# ESP_Link.net
KiCad netlist of a schematic drawn in Altium Designer
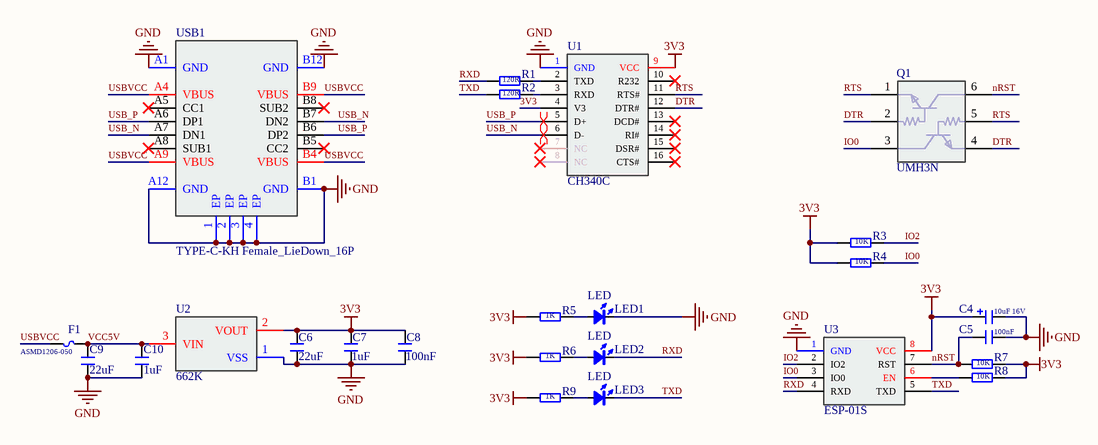
[diagram p0: ESP_Link.SchDoc]

(export (version "E")
  (design (tool "Eeschema 10.0.6"))
  (components
    (comp (ref "C4")
      (value "10uF 16V")
      (footprint "3216TantalumCap")
      (description "3216钽电容")
      (libsource (lib "IntegratedDevices") (part "3216TantalumCap"))
    )
    (comp (ref "C5")
      (value "100nF")
      (footprint "C0603")
      (description "电容-0603")
      (libsource (lib "IntegratedDevices") (part "C0603"))
    )
    (comp (ref "C6")
      (value "22uF")
      (footprint "C0603")
      (description "电容-0603")
      (libsource (lib "IntegratedDevices") (part "C0603"))
    )
    (comp (ref "C7")
      (value "1uF")
      (footprint "C0603")
      (description "电容-0603")
      (libsource (lib "IntegratedDevices") (part "C0603"))
    )
    (comp (ref "C8")
      (value "100nF")
      (footprint "C0603")
      (description "电容-0603")
      (libsource (lib "IntegratedDevices") (part "C0603"))
    )
    (comp (ref "C9")
      (value "22uF")
      (footprint "C0603")
      (description "电容-0603")
      (libsource (lib "IntegratedDevices") (part "C0603"))
    )
    (comp (ref "C10")
      (value "1uF")
      (footprint "C0603")
      (description "电容-0603")
      (libsource (lib "IntegratedDevices") (part "C0603"))
    )
    (comp (ref "F1")
      (value "ASMD1206-050")
      (footprint "ASMD1206-050")
      (description "自恢复保险丝")
      (libsource (lib "IntegratedDevices") (part "ASMD1206-050"))
    )
    (comp (ref "LED1")
      (value "LED")
      (footprint "LED_0603")
      (libsource (lib "IntegratedDevices") (part "LED_0603"))
    )
    (comp (ref "LED2")
      (value "LED")
      (footprint "LED_0603")
      (libsource (lib "IntegratedDevices") (part "LED_0603"))
    )
    (comp (ref "LED3")
      (value "LED")
      (footprint "LED_0603")
      (libsource (lib "IntegratedDevices") (part "LED_0603"))
    )
    (comp (ref "Q1")
      (value "UMH3N")
      (footprint "UMH3N")
      (description "2个NPN预偏压式(双) 100mA 50V")
      (libsource (lib "IntegratedDevices") (part "UMH3N"))
    )
    (comp (ref "R1")
      (value "120R")
      (footprint "R0603")
      (description "电阻-0603")
      (libsource (lib "IntegratedDevices") (part "R0603"))
    )
    (comp (ref "R2")
      (value "120R")
      (footprint "R0603")
      (description "电阻-0603")
      (libsource (lib "IntegratedDevices") (part "R0603"))
    )
    (comp (ref "R3")
      (value "10K")
      (footprint "R0603")
      (description "电阻-0603")
      (libsource (lib "IntegratedDevices") (part "R0603"))
    )
    (comp (ref "R4")
      (value "10K")
      (footprint "R0603")
      (description "电阻-0603")
      (libsource (lib "IntegratedDevices") (part "R0603"))
    )
    (comp (ref "R5")
      (value "1K")
      (footprint "R0603")
      (description "电阻-0603")
      (libsource (lib "IntegratedDevices") (part "R0603"))
    )
    (comp (ref "R6")
      (value "1K")
      (footprint "R0603")
      (description "电阻-0603")
      (libsource (lib "IntegratedDevices") (part "R0603"))
    )
    (comp (ref "R7")
      (value "10K")
      (footprint "R0603")
      (description "电阻-0603")
      (libsource (lib "IntegratedDevices") (part "R0603"))
    )
    (comp (ref "R8")
      (value "10K")
      (footprint "R0603")
      (description "电阻-0603")
      (libsource (lib "IntegratedDevices") (part "R0603"))
    )
    (comp (ref "R9")
      (value "1K")
      (footprint "R0603")
      (description "电阻-0603")
      (libsource (lib "IntegratedDevices") (part "R0603"))
    )
    (comp (ref "U1")
      (value "CH340C")
      (footprint "CH340C")
      (libsource (lib "IntegratedDevices") (part "CH340C"))
    )
    (comp (ref "U2")
      (value "662K")
      (footprint "662K")
      (description "线性稳压器LDO MaxIN: 6V  OUT: 3.3V")
      (libsource (lib "IntegratedDevices") (part "662K"))
    )
    (comp (ref "U3")
      (value "ESP-01S")
      (footprint "ESP-01S-NoSlik")
      (description "ESP01S开发板")
      (libsource (lib "IntegratedDevices") (part "ESP-01S"))
    )
    (comp (ref "USB1")
      (value "TYPE-C-KH Female_LieDown_16P")
      (footprint "TYPE-C-KH Female_LieDown_16P")
      (description "Type-C母座_卧贴_16P")
      (libsource (lib "IntegratedDevices") (part "TYPE-C-KH Female_LieDown_16P"))
    )
  )
  (nets
    (net (code "1") (name "/DTR") (class "Default")
      (node (ref "Q1") (pin "2") (pinfunction "B_2") (pintype "passive"))
      (node (ref "Q1") (pin "4") (pinfunction "E_4") (pintype "passive"))
      (node (ref "U1") (pin "12") (pinfunction "DTR#_12") (pintype "passive"))
    )
    (net (code "2") (name "/IO0") (class "Default")
      (node (ref "Q1") (pin "3") (pinfunction "C_3") (pintype "passive"))
      (node (ref "R4") (pin "2") (pinfunction "2_2") (pintype "passive"))
      (node (ref "U3") (pin "3") (pinfunction "IO0_3") (pintype "passive"))
    )
    (net (code "3") (name "/IO2") (class "Default")
      (node (ref "R3") (pin "2") (pinfunction "2_2") (pintype "passive"))
      (node (ref "U3") (pin "2") (pinfunction "IO2_2") (pintype "passive"))
    )
    (net (code "4") (name "/RTS") (class "Default")
      (node (ref "Q1") (pin "1") (pinfunction "E_1") (pintype "passive"))
      (node (ref "Q1") (pin "5") (pinfunction "B_5") (pintype "passive"))
      (node (ref "U1") (pin "11") (pinfunction "RTS#_11") (pintype "passive"))
    )
    (net (code "5") (name "/RXD") (class "Default")
      (node (ref "LED2") (pin "2") (pinfunction "K_2") (pintype "passive"))
      (node (ref "R1") (pin "2") (pinfunction "2_2") (pintype "passive"))
      (node (ref "U3") (pin "4") (pinfunction "RXD_4") (pintype "passive"))
    )
    (net (code "6") (name "/TXD") (class "Default")
      (node (ref "LED3") (pin "2") (pinfunction "K_2") (pintype "passive"))
      (node (ref "R2") (pin "2") (pinfunction "2_2") (pintype "passive"))
      (node (ref "U3") (pin "5") (pinfunction "TXD_5") (pintype "passive"))
    )
    (net (code "7") (name "/USBVCC") (class "Default")
      (node (ref "F1") (pin "2") (pinfunction "2_2") (pintype "passive"))
      (node (ref "USB1") (pin "A4") (pinfunction "VBUS_A4") (pintype "passive"))
      (node (ref "USB1") (pin "A9") (pinfunction "VBUS_A9") (pintype "passive"))
      (node (ref "USB1") (pin "B4") (pinfunction "VBUS_B4") (pintype "passive"))
      (node (ref "USB1") (pin "B9") (pinfunction "VBUS_B9") (pintype "passive"))
    )
    (net (code "8") (name "/USB_N") (class "Default")
      (node (ref "U1") (pin "6") (pinfunction "D-_6") (pintype "passive"))
      (node (ref "USB1") (pin "A7") (pinfunction "DN1_A7") (pintype "passive"))
      (node (ref "USB1") (pin "B7") (pinfunction "DN2_B7") (pintype "passive"))
    )
    (net (code "9") (name "/USB_P") (class "Default")
      (node (ref "U1") (pin "5") (pinfunction "D+_5") (pintype "passive"))
      (node (ref "USB1") (pin "A6") (pinfunction "DP1_A6") (pintype "passive"))
      (node (ref "USB1") (pin "B6") (pinfunction "DP2_B6") (pintype "passive"))
    )
    (net (code "10") (name "/VCC5V") (class "Default")
      (node (ref "C10") (pin "2") (pinfunction "2_2") (pintype "passive"))
      (node (ref "C9") (pin "2") (pinfunction "2_2") (pintype "passive"))
      (node (ref "F1") (pin "1") (pinfunction "1_1") (pintype "passive"))
      (node (ref "U2") (pin "3") (pinfunction "VIN_3") (pintype "passive"))
    )
    (net (code "11") (name "/nRST") (class "Default")
      (node (ref "C5") (pin "2") (pinfunction "2_2") (pintype "passive"))
      (node (ref "Q1") (pin "6") (pinfunction "C_6") (pintype "passive"))
      (node (ref "R7") (pin "1") (pinfunction "1_1") (pintype "passive"))
      (node (ref "U3") (pin "7") (pinfunction "RST_7") (pintype "passive"))
    )
    (net (code "12") (name "3V3") (class "Default")
      (node (ref "C4") (pin "1") (pinfunction "1_1") (pintype "passive"))
      (node (ref "C6") (pin "2") (pinfunction "2_2") (pintype "passive"))
      (node (ref "C7") (pin "2") (pinfunction "2_2") (pintype "passive"))
      (node (ref "C8") (pin "2") (pinfunction "2_2") (pintype "passive"))
      (node (ref "R3") (pin "1") (pinfunction "1_1") (pintype "passive"))
      (node (ref "R4") (pin "1") (pinfunction "1_1") (pintype "passive"))
      (node (ref "R5") (pin "1") (pinfunction "1_1") (pintype "passive"))
      (node (ref "R6") (pin "1") (pinfunction "1_1") (pintype "passive"))
      (node (ref "R7") (pin "2") (pinfunction "2_2") (pintype "passive"))
      (node (ref "R8") (pin "2") (pinfunction "2_2") (pintype "passive"))
      (node (ref "R9") (pin "1") (pinfunction "1_1") (pintype "passive"))
      (node (ref "U1") (pin "4") (pinfunction "V3_4") (pintype "passive"))
      (node (ref "U1") (pin "9") (pinfunction "VCC_9") (pintype "passive"))
      (node (ref "U2") (pin "2") (pinfunction "VOUT_2") (pintype "passive"))
      (node (ref "U3") (pin "8") (pinfunction "VCC_8") (pintype "passive"))
    )
    (net (code "13") (name "GND") (class "Default")
      (node (ref "C10") (pin "1") (pinfunction "1_1") (pintype "passive"))
      (node (ref "C4") (pin "2") (pinfunction "2_2") (pintype "passive"))
      (node (ref "C5") (pin "1") (pinfunction "1_1") (pintype "passive"))
      (node (ref "C6") (pin "1") (pinfunction "1_1") (pintype "passive"))
      (node (ref "C7") (pin "1") (pinfunction "1_1") (pintype "passive"))
      (node (ref "C8") (pin "1") (pinfunction "1_1") (pintype "passive"))
      (node (ref "C9") (pin "1") (pinfunction "1_1") (pintype "passive"))
      (node (ref "LED1") (pin "2") (pinfunction "K_2") (pintype "passive"))
      (node (ref "U1") (pin "1") (pinfunction "GND_1") (pintype "passive"))
      (node (ref "U2") (pin "1") (pinfunction "VSS_1") (pintype "passive"))
      (node (ref "U3") (pin "1") (pinfunction "GND_1") (pintype "passive"))
      (node (ref "USB1") (pin "1") (pinfunction "EP_1") (pintype "passive"))
      (node (ref "USB1") (pin "2") (pinfunction "EP_2") (pintype "passive"))
      (node (ref "USB1") (pin "3") (pinfunction "EP_3") (pintype "passive"))
      (node (ref "USB1") (pin "4") (pinfunction "EP_4") (pintype "passive"))
      (node (ref "USB1") (pin "A1") (pinfunction "GND_A1") (pintype "passive"))
      (node (ref "USB1") (pin "A12") (pinfunction "GND_A12") (pintype "passive"))
      (node (ref "USB1") (pin "B1") (pinfunction "GND_B1") (pintype "passive"))
      (node (ref "USB1") (pin "B12") (pinfunction "GND_B12") (pintype "passive"))
    )
    (net (code "14") (name "Net-(LED1-A)") (class "Default")
      (node (ref "LED1") (pin "1") (pinfunction "A_1") (pintype "passive"))
      (node (ref "R5") (pin "2") (pinfunction "2_2") (pintype "passive"))
    )
    (net (code "15") (name "Net-(LED2-A)") (class "Default")
      (node (ref "LED2") (pin "1") (pinfunction "A_1") (pintype "passive"))
      (node (ref "R6") (pin "2") (pinfunction "2_2") (pintype "passive"))
    )
    (net (code "16") (name "Net-(LED3-A)") (class "Default")
      (node (ref "LED3") (pin "1") (pinfunction "A_1") (pintype "passive"))
      (node (ref "R9") (pin "2") (pinfunction "2_2") (pintype "passive"))
    )
    (net (code "17") (name "Net-(U1-RXD)") (class "Default")
      (node (ref "R2") (pin "1") (pinfunction "1_1") (pintype "passive"))
      (node (ref "U1") (pin "3") (pinfunction "RXD_3") (pintype "passive"))
    )
    (net (code "18") (name "Net-(U1-TXD)") (class "Default")
      (node (ref "R1") (pin "1") (pinfunction "1_1") (pintype "passive"))
      (node (ref "U1") (pin "2") (pinfunction "TXD_2") (pintype "passive"))
    )
    (net (code "19") (name "Net-(U3-EN)") (class "Default")
      (node (ref "R8") (pin "1") (pinfunction "1_1") (pintype "passive"))
      (node (ref "U3") (pin "6") (pinfunction "EN_6") (pintype "passive"))
    )
    (net (code "20") (name "unconnected-(U1-CTS#-Pad16)") (class "Default")
      (node (ref "U1") (pin "16") (pinfunction "CTS#_16") (pintype "passive+no_connect"))
    )
    (net (code "21") (name "unconnected-(U1-DCD#-Pad13)") (class "Default")
      (node (ref "U1") (pin "13") (pinfunction "DCD#_13") (pintype "passive+no_connect"))
    )
    (net (code "22") (name "unconnected-(U1-DSR#-Pad15)") (class "Default")
      (node (ref "U1") (pin "15") (pinfunction "DSR#_15") (pintype "passive+no_connect"))
    )
    (net (code "23") (name "unconnected-(U1-NC-Pad7)") (class "Default")
      (node (ref "U1") (pin "7") (pinfunction "NC_7") (pintype "passive+no_connect"))
    )
    (net (code "24") (name "unconnected-(U1-NC-Pad8)") (class "Default")
      (node (ref "U1") (pin "8") (pinfunction "NC_8") (pintype "passive+no_connect"))
    )
    (net (code "25") (name "unconnected-(U1-R232-Pad10)") (class "Default")
      (node (ref "U1") (pin "10") (pinfunction "R232_10") (pintype "passive+no_connect"))
    )
    (net (code "26") (name "unconnected-(U1-RI#-Pad14)") (class "Default")
      (node (ref "U1") (pin "14") (pinfunction "RI#_14") (pintype "passive+no_connect"))
    )
    (net (code "27") (name "unconnected-(USB1-CC1-PadA5)") (class "Default")
      (node (ref "USB1") (pin "A5") (pinfunction "CC1_A5") (pintype "passive+no_connect"))
    )
    (net (code "28") (name "unconnected-(USB1-CC2-PadB5)") (class "Default")
      (node (ref "USB1") (pin "B5") (pinfunction "CC2_B5") (pintype "passive+no_connect"))
    )
    (net (code "29") (name "unconnected-(USB1-SUB1-PadA8)") (class "Default")
      (node (ref "USB1") (pin "A8") (pinfunction "SUB1_A8") (pintype "passive+no_connect"))
    )
    (net (code "30") (name "unconnected-(USB1-SUB2-PadB8)") (class "Default")
      (node (ref "USB1") (pin "B8") (pinfunction "SUB2_B8") (pintype "passive+no_connect"))
    )
  )
)
